# Rigid-QFN-2.net
KiCad netlist of a schematic drawn in Altium Designer
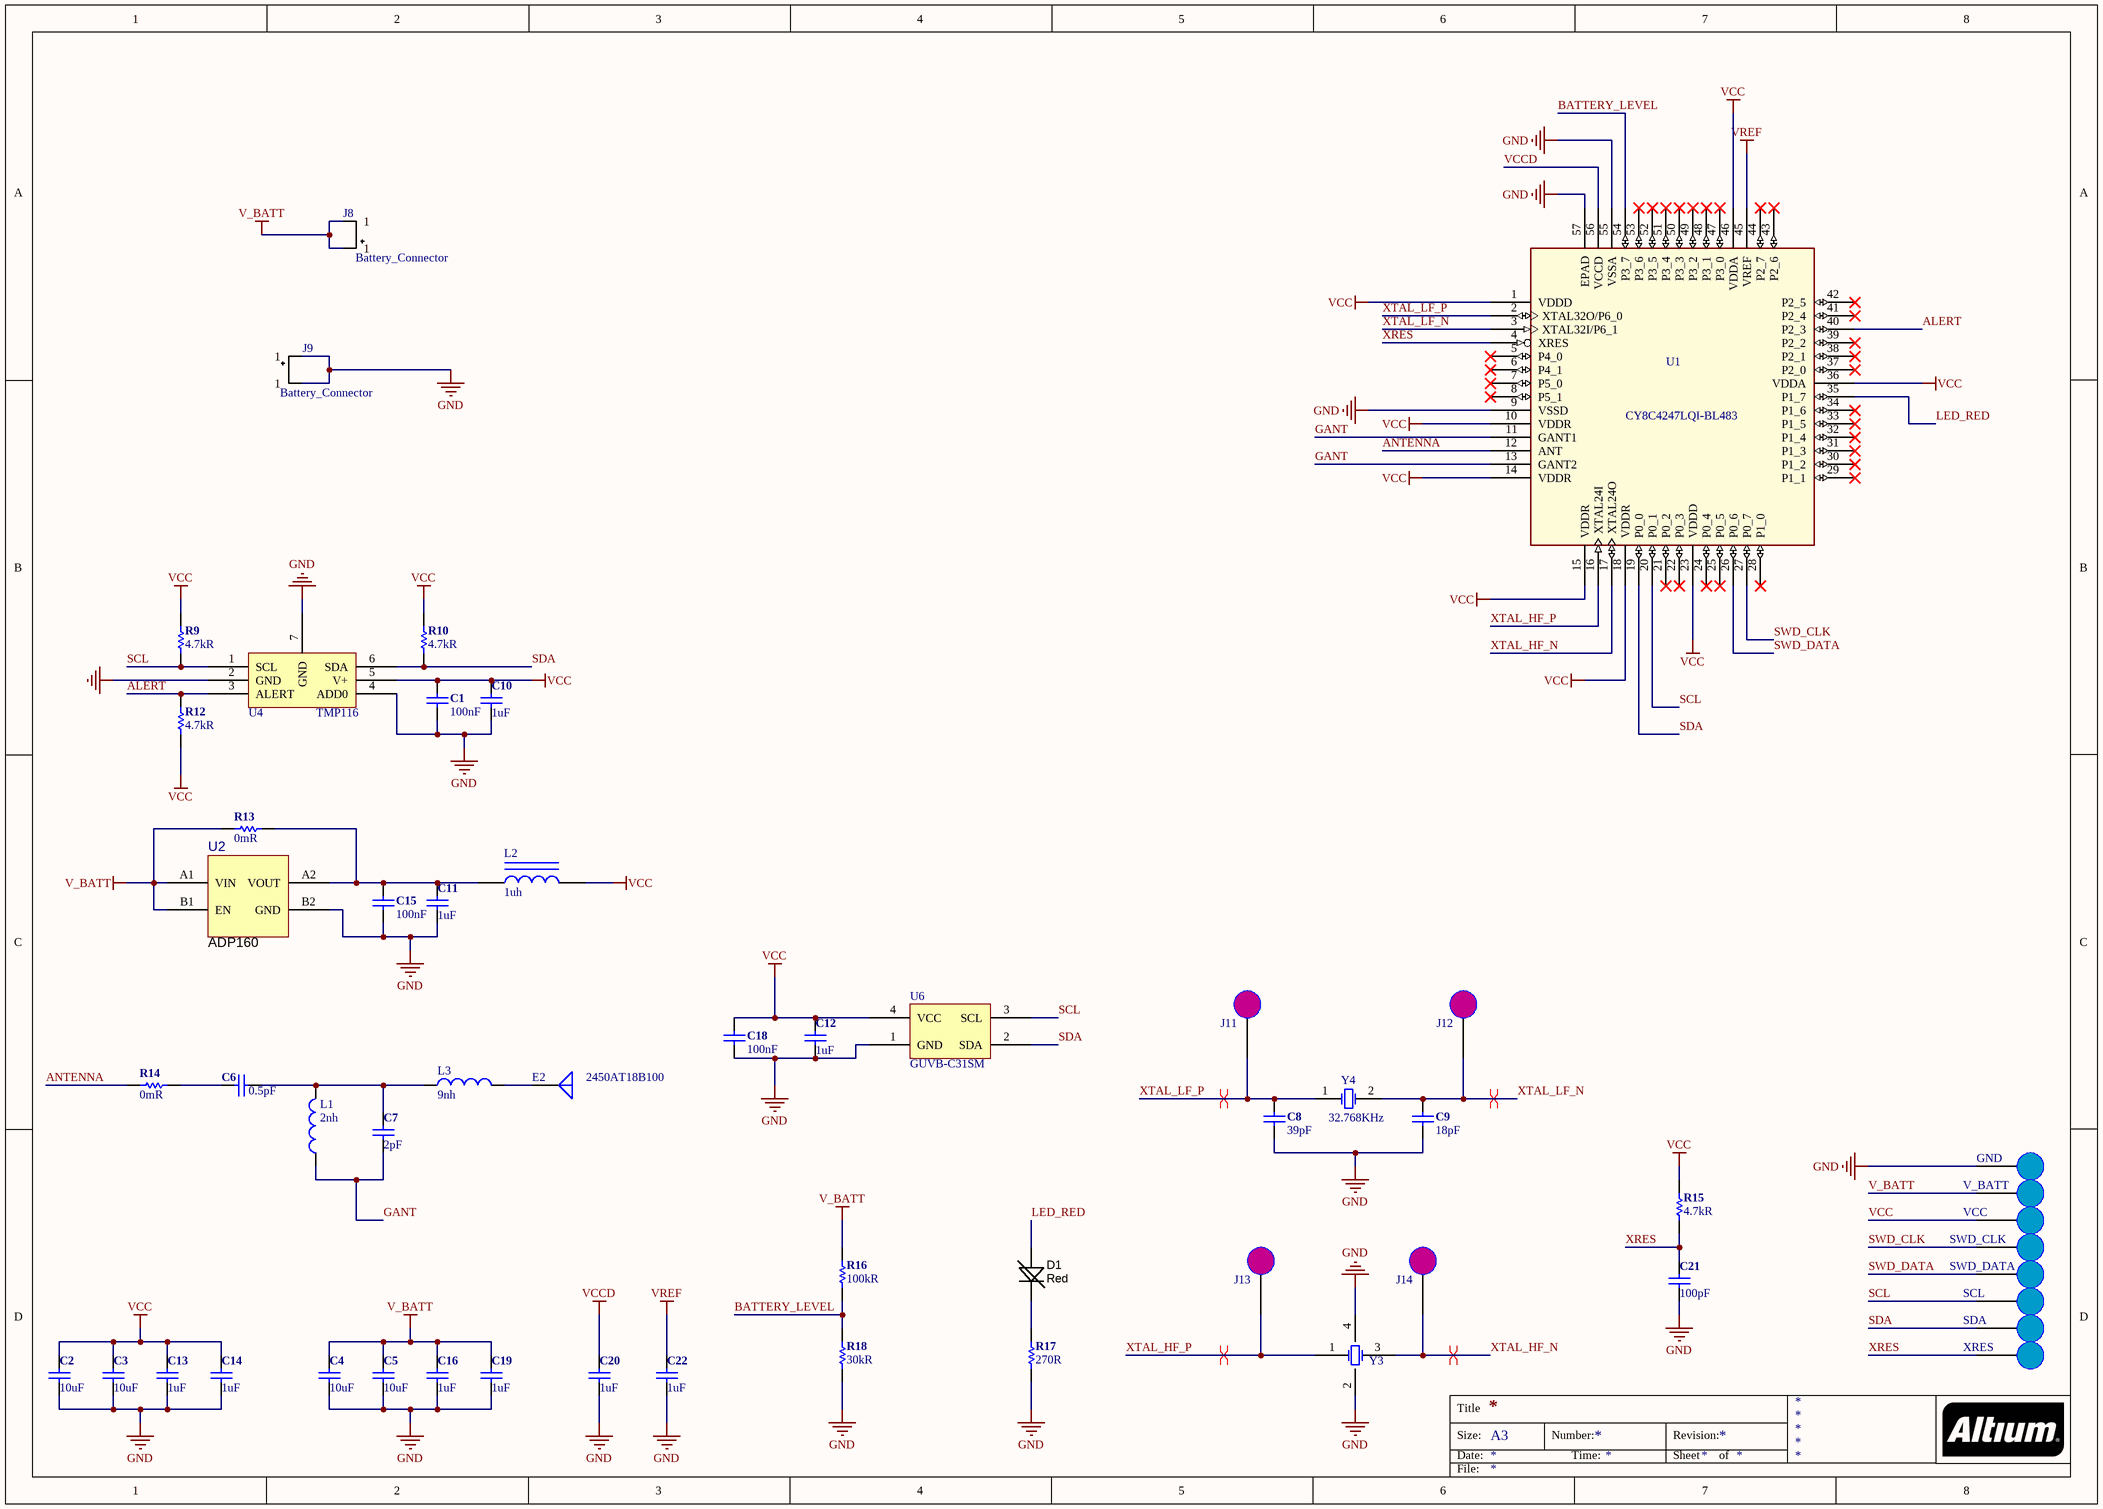
[diagram p0: Rigid-QFN-2.SchDoc]

(export (version "E")
  (design (tool "Eeschema 10.0.6"))
  (components
    (comp (ref "C1")
      (value "100nF")
      (footprint "CAP_0402(1005)_M")
      (description "___ OHM ___ mW 0402(1005) SMD")
      (fields
        (field (name "MANUFACTURER") "Yageo")
        (field (name "MANUFACTURER PART NUMBER") "CC0402ZRY5V6BB104")
      )
      (libsource (lib "tempsensor") (part "C-0402(1005)"))
    )
    (comp (ref "C2")
      (value "10uF")
      (footprint "CAP_0402(1005)_M")
      (description "___ OHM ___ mW 0402(1005) SMD")
      (fields
        (field (name "MANUFACTURER") "Murata")
        (field (name "MANUFACTURER PART NUMBER") "GRM155R60J106ME15D")
      )
      (libsource (lib "tempsensor") (part "C-0402(1005)"))
    )
    (comp (ref "C3")
      (value "10uF")
      (footprint "CAP_0402(1005)_M")
      (description "___ OHM ___ mW 0402(1005) SMD")
      (fields
        (field (name "MANUFACTURER") "Murata")
        (field (name "MANUFACTURER PART NUMBER") "GRM155R60J106ME15D")
      )
      (libsource (lib "tempsensor") (part "C-0402(1005)"))
    )
    (comp (ref "C4")
      (value "10uF")
      (footprint "CAP_0402(1005)_M")
      (description "___ OHM ___ mW 0402(1005) SMD")
      (fields
        (field (name "MANUFACTURER") "Murata")
        (field (name "MANUFACTURER PART NUMBER") "GRM155R60J106ME15D")
      )
      (libsource (lib "tempsensor") (part "C-0402(1005)"))
    )
    (comp (ref "C5")
      (value "10uF")
      (footprint "CAP_0402(1005)_M")
      (description "___ OHM ___ mW 0402(1005) SMD")
      (fields
        (field (name "MANUFACTURER") "Murata")
        (field (name "MANUFACTURER PART NUMBER") "GRM155R60J106ME15D")
      )
      (libsource (lib "tempsensor") (part "C-0402(1005)"))
    )
    (comp (ref "C6")
      (value "0.5pF")
      (footprint "CAP_0402(1005)_M")
      (description "___ OHM ___ mW 0402(1005) SMD")
      (fields
        (field (name "MANUFACTURER") "Murata")
        (field (name "MANUFACTURER PART NUMBER") "GJM1555C1HR50WB01D")
      )
      (libsource (lib "tempsensor") (part "C-0402(1005)"))
    )
    (comp (ref "C7")
      (value "2pF")
      (footprint "CAP_0402(1005)_M")
      (description "___ OHM ___ mW 0402(1005) SMD")
      (fields
        (field (name "MANUFACTURER") "Murata")
        (field (name "MANUFACTURER PART NUMBER") "GJM1555C1H2R0BB01D")
      )
      (libsource (lib "tempsensor") (part "C-0402(1005)"))
    )
    (comp (ref "C8")
      (value "39pF")
      (footprint "CAP_0402(1005)_M")
      (description "___ OHM ___ mW 0402(1005) SMD")
      (fields
        (field (name "MANUFACTURER") "KEMET")
        (field (name "MANUFACTURER PART NUMBER") "CBR04C390F5GAC")
      )
      (libsource (lib "tempsensor") (part "C-0402(1005)"))
    )
    (comp (ref "C9")
      (value "18pF")
      (footprint "CAP_0402(1005)_M")
      (description "___ OHM ___ mW 0402(1005) SMD")
      (fields
        (field (name "MANUFACTURER") "Murata")
        (field (name "MANUFACTURER PART NUMBER") "GJM1555C1H180FB01D")
      )
      (libsource (lib "tempsensor") (part "C-0402(1005)"))
    )
    (comp (ref "C10")
      (value "1uF")
      (footprint "CAP_0402(1005)_M")
      (description "___ OHM ___ mW 0402(1005) SMD")
      (fields
        (field (name "MANUFACTURER") "KEMET")
        (field (name "MANUFACTURER PART NUMBER") "C0402C105K8PACTU")
      )
      (libsource (lib "tempsensor") (part "C-0402(1005)"))
    )
    (comp (ref "C11")
      (value "1uF")
      (footprint "CAP_0402(1005)_M")
      (description "___ OHM ___ mW 0402(1005) SMD")
      (fields
        (field (name "MANUFACTURER") "KEMET")
        (field (name "MANUFACTURER PART NUMBER") "C0402C105K8PACTU")
      )
      (libsource (lib "tempsensor") (part "C-0402(1005)"))
    )
    (comp (ref "C12")
      (value "1uF")
      (footprint "CAP_0402(1005)_M")
      (description "___ OHM ___ mW 0402(1005) SMD")
      (fields
        (field (name "MANUFACTURER") "KEMET")
        (field (name "MANUFACTURER PART NUMBER") "C0402C105K8PACTU")
      )
      (libsource (lib "tempsensor") (part "C-0402(1005)"))
    )
    (comp (ref "C13")
      (value "1uF")
      (footprint "CAP_0402(1005)_M")
      (description "___ OHM ___ mW 0402(1005) SMD")
      (fields
        (field (name "MANUFACTURER") "KEMET")
        (field (name "MANUFACTURER PART NUMBER") "C0402C105K8PACTU")
      )
      (libsource (lib "tempsensor") (part "C-0402(1005)"))
    )
    (comp (ref "C14")
      (value "1uF")
      (footprint "CAP_0402(1005)_M")
      (description "___ OHM ___ mW 0402(1005) SMD")
      (fields
        (field (name "MANUFACTURER") "KEMET")
        (field (name "MANUFACTURER PART NUMBER") "C0402C105K8PACTU")
      )
      (libsource (lib "tempsensor") (part "C-0402(1005)"))
    )
    (comp (ref "C15")
      (value "100nF")
      (footprint "CAP_0402(1005)_M")
      (description "___ OHM ___ mW 0402(1005) SMD")
      (fields
        (field (name "MANUFACTURER") "Yageo")
        (field (name "MANUFACTURER PART NUMBER") "CC0402ZRY5V6BB104")
      )
      (libsource (lib "tempsensor") (part "C-0402(1005)"))
    )
    (comp (ref "C16")
      (value "1uF")
      (footprint "CAP_0402(1005)_M")
      (description "___ OHM ___ mW 0402(1005) SMD")
      (fields
        (field (name "MANUFACTURER") "KEMET")
        (field (name "MANUFACTURER PART NUMBER") "C0402C105K8PACTU")
      )
      (libsource (lib "tempsensor") (part "C-0402(1005)"))
    )
    (comp (ref "C18")
      (value "100nF")
      (footprint "CAP_0402(1005)_M")
      (description "___ OHM ___ mW 0402(1005) SMD")
      (fields
        (field (name "MANUFACTURER") "Yageo")
        (field (name "MANUFACTURER PART NUMBER") "CC0402ZRY5V6BB104")
      )
      (libsource (lib "tempsensor") (part "C-0402(1005)"))
    )
    (comp (ref "C19")
      (value "1uF")
      (footprint "CAP_0402(1005)_M")
      (description "___ OHM ___ mW 0402(1005) SMD")
      (fields
        (field (name "MANUFACTURER") "KEMET")
        (field (name "MANUFACTURER PART NUMBER") "C0402C105K8PACTU")
      )
      (libsource (lib "tempsensor") (part "C-0402(1005)"))
    )
    (comp (ref "C20")
      (value "1uF")
      (footprint "CAP_0402(1005)_M")
      (description "___ OHM ___ mW 0402(1005) SMD")
      (fields
        (field (name "MANUFACTURER") "KEMET")
        (field (name "MANUFACTURER PART NUMBER") "C0402C105K8PACTU")
      )
      (libsource (lib "tempsensor") (part "C-0402(1005)"))
    )
    (comp (ref "C21")
      (value "100pF")
      (footprint "CAP_0402(1005)_M")
      (description "___ OHM ___ mW 0402(1005) SMD")
      (fields
        (field (name "MANUFACTURER") "Wurth Electronics")
        (field (name "MANUFACTURER PART NUMBER") "885012005013")
      )
      (libsource (lib "tempsensor") (part "C-0402(1005)"))
    )
    (comp (ref "C22")
      (value "1uF")
      (footprint "CAP_0402(1005)_M")
      (description "___ OHM ___ mW 0402(1005) SMD")
      (fields
        (field (name "MANUFACTURER") "KEMET")
        (field (name "MANUFACTURER PART NUMBER") "C0402C105K8PACTU")
      )
      (libsource (lib "tempsensor") (part "C-0402(1005)"))
    )
    (comp (ref "D1")
      (value "Red")
      (footprint "LED_0402(1005)")
      (description "LED, 0402(1005) SMD")
      (fields
        (field (name "MANUFACTURER") "Kingbright")
        (field (name "MANUFACTURER PART NUMBER") "APHHS1005SURCK")
      )
      (libsource (lib "tempsensor") (part "LED_0402(1005)"))
    )
    (comp (ref "E2")
      (value "2450AT18B100")
      (footprint "2450AT18B100")
      (description "2.4 GHz BLE Antenna")
      (fields
        (field (name "MANUFACTURER") "Johanson")
        (field (name "MANUFACTURER PART NUMBER") "2450AT18B100E")
      )
      (libsource (lib "tempsensor") (part "2450AT18B100"))
    )
    (comp (ref "GND")
      (value "Probe-Pin Pad")
      (footprint "Pogo-Pin-Pad")
      (libsource (lib "tempsensor") (part "Probe-Pin Pad"))
    )
    (comp (ref "J8")
      (value "Battery_Connector")
      (footprint "Battery_PAD")
      (libsource (lib "tempsensor") (part "Battery_Connector"))
    )
    (comp (ref "J9")
      (value "Battery_Connector")
      (footprint "Battery_PAD")
      (libsource (lib "tempsensor") (part "Battery_Connector"))
    )
    (comp (ref "J11")
      (value "Probe-CLOCK")
      (footprint "Pogo-CLOCK-PAD")
      (libsource (lib "tempsensor") (part "Probe-CLOCK"))
    )
    (comp (ref "J12")
      (value "Probe-CLOCK")
      (footprint "Pogo-CLOCK-PAD")
      (libsource (lib "tempsensor") (part "Probe-CLOCK"))
    )
    (comp (ref "J13")
      (value "Probe-CLOCK")
      (footprint "Pogo-CLOCK-PAD")
      (libsource (lib "tempsensor") (part "Probe-CLOCK"))
    )
    (comp (ref "J14")
      (value "Probe-CLOCK")
      (footprint "Pogo-CLOCK-PAD")
      (libsource (lib "tempsensor") (part "Probe-CLOCK"))
    )
    (comp (ref "L1")
      (value "2nh")
      (footprint "IND_0402(1005)_M")
      (fields
        (field (name "MANUFACTURER") "Abracon")
        (field (name "MANUFACTURER PART NUMBER") "AISC-0402-2N0J-T")
        (field (name "TOLERANCE") "5%")
      )
      (libsource (lib "tempsensor") (part "I-0402(1005)"))
    )
    (comp (ref "L2")
      (value "1uh")
      (footprint "IND_0402(1005)_M")
      (description "Magnetic-Core Inductor")
      (fields
        (field (name "MANUFACTURER") "TDK")
        (field (name "MANUFACTURER PART NUMBER") "MLZ1005M1R0WT000")
      )
      (libsource (lib "tempsensor") (part "Inductor Iron"))
    )
    (comp (ref "L3")
      (value "9nh")
      (footprint "IND_0402(1005)_M")
      (fields
        (field (name "MANUFACTURER") "Murata")
        (field (name "MANUFACTURER PART NUMBER") "LQW15AN9N0G80D")
        (field (name "TOLERANCE") "2%")
      )
      (libsource (lib "tempsensor") (part "I-0402(1005)"))
    )
    (comp (ref "R9")
      (value "4.7kR")
      (footprint "RES_0402(1005)_M")
      (description "___ OHM ___ mW 0402(1005) SMD")
      (fields
        (field (name "MANUFACTURER") "Yageo")
        (field (name "MANUFACTURER PART NUMBER") "RC0402JR-074K7P")
      )
      (libsource (lib "tempsensor") (part "R-0402(1005)"))
    )
    (comp (ref "R10")
      (value "4.7kR")
      (footprint "RES_0402(1005)_M")
      (description "___ OHM ___ mW 0402(1005) SMD")
      (fields
        (field (name "MANUFACTURER") "Yageo")
        (field (name "MANUFACTURER PART NUMBER") "RC0402JR-074K7P")
      )
      (libsource (lib "tempsensor") (part "R-0402(1005)"))
    )
    (comp (ref "R12")
      (value "4.7kR")
      (footprint "RES_0402(1005)_M")
      (description "___ OHM ___ mW 0402(1005) SMD")
      (fields
        (field (name "MANUFACTURER") "Yageo")
        (field (name "MANUFACTURER PART NUMBER") "RC0402JR-074K7P")
      )
      (libsource (lib "tempsensor") (part "R-0402(1005)"))
    )
    (comp (ref "R13")
      (value "0mR")
      (footprint "RES_0402(1005)_M")
      (description "___ OHM ___ mW 0402(1005) SMD")
      (fields
        (field (name "MANUFACTURER") "Yageo")
        (field (name "MANUFACTURER PART NUMBER") "AC0402JR-070RL")
      )
      (libsource (lib "tempsensor") (part "R-0402(1005)"))
    )
    (comp (ref "R14")
      (value "0mR")
      (footprint "RES_0402(1005)_M")
      (description "___ OHM ___ mW 0402(1005) SMD")
      (fields
        (field (name "MANUFACTURER") "Yageo")
        (field (name "MANUFACTURER PART NUMBER") "AC0402JR-070RL")
      )
      (libsource (lib "tempsensor") (part "R-0402(1005)"))
    )
    (comp (ref "R15")
      (value "4.7kR")
      (footprint "RES_0402(1005)_M")
      (description "___ OHM ___ mW 0402(1005) SMD")
      (fields
        (field (name "MANUFACTURER") "Yageo")
        (field (name "MANUFACTURER PART NUMBER") "RC0402JR-074K7P")
      )
      (libsource (lib "tempsensor") (part "R-0402(1005)"))
    )
    (comp (ref "R16")
      (value "100kR")
      (footprint "RES_0402(1005)_M")
      (description "___ OHM ___ mW 0402(1005) SMD")
      (fields
        (field (name "MANUFACTURER") "Yageo")
        (field (name "MANUFACTURER PART NUMBER") "AC0402JR-07100KL")
      )
      (libsource (lib "tempsensor") (part "R-0402(1005)"))
    )
    (comp (ref "R17")
      (value "270R")
      (footprint "RES_0402(1005)_M")
      (description "___ OHM ___ mW 0402(1005) SMD")
      (fields
        (field (name "MANUFACTURER") "Yageo")
        (field (name "MANUFACTURER PART NUMBER") "RC0402JR-07270RL")
      )
      (libsource (lib "tempsensor") (part "R-0402(1005)"))
    )
    (comp (ref "R18")
      (value "30kR")
      (footprint "RES_0402(1005)_M")
      (description "___ OHM ___ mW 0402(1005) SMD")
      (fields
        (field (name "MANUFACTURER") "Yageo")
        (field (name "MANUFACTURER PART NUMBER") "RC0402JR-0730KL")
      )
      (libsource (lib "tempsensor") (part "R-0402(1005)"))
    )
    (comp (ref "SCL")
      (value "Probe-Pin Pad")
      (footprint "Pogo-Pin-Pad")
      (libsource (lib "tempsensor") (part "Probe-Pin Pad"))
    )
    (comp (ref "SDA")
      (value "Probe-Pin Pad")
      (footprint "Pogo-Pin-Pad")
      (libsource (lib "tempsensor") (part "Probe-Pin Pad"))
    )
    (comp (ref "SWD_CLK")
      (value "Probe-Pin Pad")
      (footprint "Pogo-Pin-Pad")
      (libsource (lib "tempsensor") (part "Probe-Pin Pad"))
    )
    (comp (ref "SWD_DATA")
      (value "Probe-Pin Pad")
      (footprint "Pogo-Pin-Pad")
      (libsource (lib "tempsensor") (part "Probe-Pin Pad"))
    )
    (comp (ref "U1")
      (value "CY8C4247LQI-BL483")
      (footprint "QFN40P700X700X60-57N")
      (fields (field (name "MANUFACTURER") "Cypress"))
      (libsource (lib "tempsensor") (part "CY8C4247LQI-BL483"))
    )
    (comp (ref "U2")
      (value "ADP160")
      (footprint "ADP160")
      (description "3V LDO")
      (fields
        (field (name "MANUFACTURER") "Analog Devices")
        (field (name "MANUFACTURER PART NUMBER") "ADP160ACBZ-3.0-R7")
      )
      (libsource (lib "tempsensor") (part "ADP160"))
    )
    (comp (ref "U4")
      (value "TMP116")
      (footprint "WSON-6")
      (description "TI Digital I2C Temperature Sensor")
      (fields
        (field (name "MANUFACTURER") "Texas Instruments")
        (field (name "MANUFACTURER PART NUMBER") "TMP116AIDRVT")
      )
      (libsource (lib "tempsensor") (part "TMP116"))
    )
    (comp (ref "U6")
      (value "GUVB-C31SM")
      (footprint "GUVB-C31SM")
      (libsource (lib "tempsensor") (part "GUVB-C31SM"))
    )
    (comp (ref "VCC")
      (value "Probe-Pin Pad")
      (footprint "Pogo-Pin-Pad")
      (libsource (lib "tempsensor") (part "Probe-Pin Pad"))
    )
    (comp (ref "V_BATT")
      (value "Probe-Pin Pad")
      (footprint "Pogo-Pin-Pad")
      (libsource (lib "tempsensor") (part "Probe-Pin Pad"))
    )
    (comp (ref "XRES")
      (value "Probe-Pin Pad")
      (footprint "Pogo-Pin-Pad")
      (libsource (lib "tempsensor") (part "Probe-Pin Pad"))
    )
    (comp (ref "Y3")
      (value "ECX-2236")
      (footprint "ECX-2236")
      (description "24 MHz Crystal")
      (fields
        (field (name "MANUFACTURER") "ECS International")
        (field (name "MANUFACTURER PART NUMBER") "ECS-240-8-36CKM-TR")
      )
      (libsource (lib "tempsensor") (part "ECX-2236"))
    )
    (comp (ref "Y4")
      (value "32.768KHz")
      (footprint "ABS05")
      (description "Crystal Oscillator")
      (fields
        (field (name "MANUFACTURER") "Abracon")
        (field (name "MANUFACTURER PART NUMBER") "ABS05-32.768KHZ-T")
      )
      (libsource (lib "tempsensor") (part "ABS05"))
    )
  )
  (nets
    (net (code "1") (name "/ALERT") (class "Default")
      (node (ref "R12") (pin "2") (pinfunction "2_2") (pintype "passive"))
      (node (ref "U1") (pin "40") (pinfunction "P2_3_40") (pintype "bidirectional"))
      (node (ref "U4") (pin "3") (pinfunction "ALERT_3") (pintype "passive"))
    )
    (net (code "2") (name "/ANTENNA") (class "Default")
      (node (ref "R14") (pin "1") (pinfunction "1_1") (pintype "passive"))
      (node (ref "U1") (pin "12") (pinfunction "ANT_12") (pintype "passive"))
    )
    (net (code "3") (name "/BATTERY_LEVEL") (class "Default")
      (node (ref "R16") (pin "2") (pinfunction "2_2") (pintype "passive"))
      (node (ref "R18") (pin "1") (pinfunction "1_1") (pintype "passive"))
      (node (ref "U1") (pin "54") (pinfunction "P3_7_54") (pintype "bidirectional"))
    )
    (net (code "4") (name "/GANT") (class "Default")
      (node (ref "C7") (pin "2") (pinfunction "2_2") (pintype "passive"))
      (node (ref "L1") (pin "1") (pinfunction "1_1") (pintype "passive"))
      (node (ref "U1") (pin "11") (pinfunction "GANT1_11") (pintype "power_in"))
      (node (ref "U1") (pin "13") (pinfunction "GANT2_13") (pintype "power_in"))
    )
    (net (code "5") (name "/LED_RED") (class "Default")
      (node (ref "D1") (pin "A") (pinfunction "A_A") (pintype "passive"))
      (node (ref "U1") (pin "35") (pinfunction "P1_7_35") (pintype "bidirectional"))
    )
    (net (code "6") (name "/SCL") (class "Default")
      (node (ref "R9") (pin "1") (pinfunction "1_1") (pintype "passive"))
      (node (ref "SCL") (pin "1") (pinfunction "1_1") (pintype "passive"))
      (node (ref "U1") (pin "20") (pinfunction "P0_1_20") (pintype "bidirectional"))
      (node (ref "U4") (pin "1") (pinfunction "SCL_1") (pintype "passive"))
      (node (ref "U6") (pin "3") (pinfunction "SCL_3") (pintype "passive"))
    )
    (net (code "7") (name "/SDA") (class "Default")
      (node (ref "R10") (pin "1") (pinfunction "1_1") (pintype "passive"))
      (node (ref "SDA") (pin "1") (pinfunction "1_1") (pintype "passive"))
      (node (ref "U1") (pin "19") (pinfunction "P0_0_19") (pintype "bidirectional"))
      (node (ref "U4") (pin "6") (pinfunction "SDA_6") (pintype "passive"))
      (node (ref "U6") (pin "2") (pinfunction "SDA_2") (pintype "passive"))
    )
    (net (code "8") (name "/SWD_CLK") (class "Default")
      (node (ref "SWD_CLK") (pin "1") (pinfunction "1_1") (pintype "passive"))
      (node (ref "U1") (pin "27") (pinfunction "P0_7_27") (pintype "bidirectional"))
    )
    (net (code "9") (name "/SWD_DATA") (class "Default")
      (node (ref "SWD_DATA") (pin "1") (pinfunction "1_1") (pintype "passive"))
      (node (ref "U1") (pin "26") (pinfunction "P0_6_26") (pintype "bidirectional"))
    )
    (net (code "10") (name "/XRES") (class "Default")
      (node (ref "C21") (pin "1") (pinfunction "1_1") (pintype "passive"))
      (node (ref "R15") (pin "2") (pinfunction "2_2") (pintype "passive"))
      (node (ref "U1") (pin "4") (pinfunction "XRES_4") (pintype "input"))
      (node (ref "XRES") (pin "1") (pinfunction "1_1") (pintype "passive"))
    )
    (net (code "11") (name "/XTAL_HF_N") (class "Default")
      (node (ref "J14") (pin "1") (pinfunction "1_1") (pintype "passive"))
      (node (ref "U1") (pin "17") (pinfunction "XTAL24O_17") (pintype "bidirectional"))
      (node (ref "Y3") (pin "3") (pinfunction "OSC2_3") (pintype "passive"))
    )
    (net (code "12") (name "/XTAL_HF_P") (class "Default")
      (node (ref "J13") (pin "1") (pinfunction "1_1") (pintype "passive"))
      (node (ref "U1") (pin "16") (pinfunction "XTAL24I_16") (pintype "input"))
      (node (ref "Y3") (pin "1") (pinfunction "OSC1_1") (pintype "passive"))
    )
    (net (code "13") (name "/XTAL_LF_N") (class "Default")
      (node (ref "C9") (pin "1") (pinfunction "1_1") (pintype "passive"))
      (node (ref "J12") (pin "1") (pinfunction "1_1") (pintype "passive"))
      (node (ref "U1") (pin "3") (pinfunction "XTAL32I/P6_1_3") (pintype "input"))
      (node (ref "Y4") (pin "2") (pinfunction "OSC2_2") (pintype "passive"))
    )
    (net (code "14") (name "/XTAL_LF_P") (class "Default")
      (node (ref "C8") (pin "1") (pinfunction "1_1") (pintype "passive"))
      (node (ref "J11") (pin "1") (pinfunction "1_1") (pintype "passive"))
      (node (ref "U1") (pin "2") (pinfunction "XTAL32O/P6_0_2") (pintype "bidirectional"))
      (node (ref "Y4") (pin "1") (pinfunction "OSC1_1") (pintype "passive"))
    )
    (net (code "15") (name "GND") (class "Default")
      (node (ref "C1") (pin "2") (pinfunction "2_2") (pintype "passive"))
      (node (ref "C10") (pin "2") (pinfunction "2_2") (pintype "passive"))
      (node (ref "C11") (pin "2") (pinfunction "2_2") (pintype "passive"))
      (node (ref "C12") (pin "2") (pinfunction "2_2") (pintype "passive"))
      (node (ref "C13") (pin "2") (pinfunction "2_2") (pintype "passive"))
      (node (ref "C14") (pin "2") (pinfunction "2_2") (pintype "passive"))
      (node (ref "C15") (pin "2") (pinfunction "2_2") (pintype "passive"))
      (node (ref "C16") (pin "2") (pinfunction "2_2") (pintype "passive"))
      (node (ref "C18") (pin "2") (pinfunction "2_2") (pintype "passive"))
      (node (ref "C19") (pin "2") (pinfunction "2_2") (pintype "passive"))
      (node (ref "C2") (pin "2") (pinfunction "2_2") (pintype "passive"))
      (node (ref "C20") (pin "2") (pinfunction "2_2") (pintype "passive"))
      (node (ref "C21") (pin "2") (pinfunction "2_2") (pintype "passive"))
      (node (ref "C22") (pin "2") (pinfunction "2_2") (pintype "passive"))
      (node (ref "C3") (pin "2") (pinfunction "2_2") (pintype "passive"))
      (node (ref "C4") (pin "2") (pinfunction "2_2") (pintype "passive"))
      (node (ref "C5") (pin "2") (pinfunction "2_2") (pintype "passive"))
      (node (ref "C8") (pin "2") (pinfunction "2_2") (pintype "passive"))
      (node (ref "C9") (pin "2") (pinfunction "2_2") (pintype "passive"))
      (node (ref "GND") (pin "1") (pinfunction "1_1") (pintype "passive"))
      (node (ref "J9") (pin "1") (pinfunction "1_1") (pintype "passive"))
      (node (ref "R17") (pin "2") (pinfunction "2_2") (pintype "passive"))
      (node (ref "R18") (pin "2") (pinfunction "2_2") (pintype "passive"))
      (node (ref "U1") (pin "55") (pinfunction "VSSA_55") (pintype "power_in"))
      (node (ref "U1") (pin "57") (pinfunction "EPAD_57") (pintype "power_in"))
      (node (ref "U1") (pin "9") (pinfunction "VSSD_9") (pintype "power_in"))
      (node (ref "U2") (pin "B2") (pinfunction "GND_B2") (pintype "passive"))
      (node (ref "U4") (pin "2") (pinfunction "GND_2") (pintype "passive"))
      (node (ref "U4") (pin "4") (pinfunction "ADD0_4") (pintype "passive"))
      (node (ref "U4") (pin "7") (pinfunction "GND_7") (pintype "passive"))
      (node (ref "U6") (pin "1") (pinfunction "GND_1") (pintype "passive"))
      (node (ref "Y3") (pin "2") (pinfunction "GND_2") (pintype "passive"))
      (node (ref "Y3") (pin "4") (pinfunction "GND_4") (pintype "passive"))
    )
    (net (code "16") (name "Net-(C6-Pad1)") (class "Default")
      (node (ref "C6") (pin "1") (pinfunction "1_1") (pintype "passive"))
      (node (ref "R14") (pin "2") (pinfunction "2_2") (pintype "passive"))
    )
    (net (code "17") (name "Net-(C6-Pad2)") (class "Default")
      (node (ref "C6") (pin "2") (pinfunction "2_2") (pintype "passive"))
      (node (ref "C7") (pin "1") (pinfunction "1_1") (pintype "passive"))
      (node (ref "L1") (pin "2") (pinfunction "2_2") (pintype "passive"))
      (node (ref "L3") (pin "1") (pinfunction "1_1") (pintype "passive"))
    )
    (net (code "18") (name "Net-(D1-PadK)") (class "Default")
      (node (ref "D1") (pin "K") (pinfunction "K_K") (pintype "passive"))
      (node (ref "R17") (pin "1") (pinfunction "1_1") (pintype "passive"))
    )
    (net (code "19") (name "Net-(E2-A)") (class "Default")
      (node (ref "E2") (pin "1") (pinfunction "A_1") (pintype "passive"))
      (node (ref "L3") (pin "2") (pinfunction "2_2") (pintype "passive"))
    )
    (net (code "20") (name "Net-(U2-VOUT)") (class "Default")
      (node (ref "C11") (pin "1") (pinfunction "1_1") (pintype "passive"))
      (node (ref "C15") (pin "1") (pinfunction "1_1") (pintype "passive"))
      (node (ref "L2") (pin "1") (pinfunction "1_1") (pintype "passive"))
      (node (ref "R13") (pin "2") (pinfunction "2_2") (pintype "passive"))
      (node (ref "U2") (pin "A2") (pinfunction "VOUT_A2") (pintype "passive"))
    )
    (net (code "21") (name "VCC") (class "Default")
      (node (ref "C1") (pin "1") (pinfunction "1_1") (pintype "passive"))
      (node (ref "C10") (pin "1") (pinfunction "1_1") (pintype "passive"))
      (node (ref "C12") (pin "1") (pinfunction "1_1") (pintype "passive"))
      (node (ref "C13") (pin "1") (pinfunction "1_1") (pintype "passive"))
      (node (ref "C14") (pin "1") (pinfunction "1_1") (pintype "passive"))
      (node (ref "C18") (pin "1") (pinfunction "1_1") (pintype "passive"))
      (node (ref "C2") (pin "1") (pinfunction "1_1") (pintype "passive"))
      (node (ref "C3") (pin "1") (pinfunction "1_1") (pintype "passive"))
      (node (ref "L2") (pin "2") (pinfunction "2_2") (pintype "passive"))
      (node (ref "R10") (pin "2") (pinfunction "2_2") (pintype "passive"))
      (node (ref "R12") (pin "1") (pinfunction "1_1") (pintype "passive"))
      (node (ref "R15") (pin "1") (pinfunction "1_1") (pintype "passive"))
      (node (ref "R9") (pin "2") (pinfunction "2_2") (pintype "passive"))
      (node (ref "U1") (pin "1") (pinfunction "VDDD_1") (pintype "power_in"))
      (node (ref "U1") (pin "10") (pinfunction "VDDR_10") (pintype "power_in"))
      (node (ref "U1") (pin "14") (pinfunction "VDDR_14") (pintype "power_in"))
      (node (ref "U1") (pin "15") (pinfunction "VDDR_15") (pintype "power_in"))
      (node (ref "U1") (pin "18") (pinfunction "VDDR_18") (pintype "power_in"))
      (node (ref "U1") (pin "23") (pinfunction "VDDD_23") (pintype "power_in"))
      (node (ref "U1") (pin "36") (pinfunction "VDDA_36") (pintype "power_in"))
      (node (ref "U1") (pin "46") (pinfunction "VDDA_46") (pintype "power_in"))
      (node (ref "U4") (pin "5") (pinfunction "V+_5") (pintype "passive"))
      (node (ref "U6") (pin "4") (pinfunction "VCC_4") (pintype "passive"))
      (node (ref "VCC") (pin "1") (pinfunction "1_1") (pintype "passive"))
    )
    (net (code "22") (name "VCCD") (class "Default")
      (node (ref "C20") (pin "1") (pinfunction "1_1") (pintype "passive"))
      (node (ref "U1") (pin "56") (pinfunction "VCCD_56") (pintype "power_in"))
    )
    (net (code "23") (name "VREF") (class "Default")
      (node (ref "C22") (pin "1") (pinfunction "1_1") (pintype "passive"))
      (node (ref "U1") (pin "45") (pinfunction "VREF_45") (pintype "power_in"))
    )
    (net (code "24") (name "V_BATT") (class "Default")
      (node (ref "C16") (pin "1") (pinfunction "1_1") (pintype "passive"))
      (node (ref "C19") (pin "1") (pinfunction "1_1") (pintype "passive"))
      (node (ref "C4") (pin "1") (pinfunction "1_1") (pintype "passive"))
      (node (ref "C5") (pin "1") (pinfunction "1_1") (pintype "passive"))
      (node (ref "J8") (pin "1") (pinfunction "1_1") (pintype "passive"))
      (node (ref "R13") (pin "1") (pinfunction "1_1") (pintype "passive"))
      (node (ref "R16") (pin "1") (pinfunction "1_1") (pintype "passive"))
      (node (ref "U2") (pin "A1") (pinfunction "VIN_A1") (pintype "passive"))
      (node (ref "U2") (pin "B1") (pinfunction "EN_B1") (pintype "passive"))
      (node (ref "V_BATT") (pin "1") (pinfunction "1_1") (pintype "passive"))
    )
    (net (code "25") (name "unconnected-(U1-P0_2-Pad21)") (class "Default")
      (node (ref "U1") (pin "21") (pinfunction "P0_2_21") (pintype "bidirectional+no_connect"))
    )
    (net (code "26") (name "unconnected-(U1-P0_3-Pad22)") (class "Default")
      (node (ref "U1") (pin "22") (pinfunction "P0_3_22") (pintype "bidirectional+no_connect"))
    )
    (net (code "27") (name "unconnected-(U1-P0_4-Pad24)") (class "Default")
      (node (ref "U1") (pin "24") (pinfunction "P0_4_24") (pintype "bidirectional+no_connect"))
    )
    (net (code "28") (name "unconnected-(U1-P0_5-Pad25)") (class "Default")
      (node (ref "U1") (pin "25") (pinfunction "P0_5_25") (pintype "bidirectional+no_connect"))
    )
    (net (code "29") (name "unconnected-(U1-P1_0-Pad28)") (class "Default")
      (node (ref "U1") (pin "28") (pinfunction "P1_0_28") (pintype "bidirectional+no_connect"))
    )
    (net (code "30") (name "unconnected-(U1-P1_1-Pad29)") (class "Default")
      (node (ref "U1") (pin "29") (pinfunction "P1_1_29") (pintype "bidirectional+no_connect"))
    )
    (net (code "31") (name "unconnected-(U1-P1_2-Pad30)") (class "Default")
      (node (ref "U1") (pin "30") (pinfunction "P1_2_30") (pintype "bidirectional+no_connect"))
    )
    (net (code "32") (name "unconnected-(U1-P1_3-Pad31)") (class "Default")
      (node (ref "U1") (pin "31") (pinfunction "P1_3_31") (pintype "bidirectional+no_connect"))
    )
    (net (code "33") (name "unconnected-(U1-P1_4-Pad32)") (class "Default")
      (node (ref "U1") (pin "32") (pinfunction "P1_4_32") (pintype "bidirectional+no_connect"))
    )
    (net (code "34") (name "unconnected-(U1-P1_5-Pad33)") (class "Default")
      (node (ref "U1") (pin "33") (pinfunction "P1_5_33") (pintype "bidirectional+no_connect"))
    )
    (net (code "35") (name "unconnected-(U1-P1_6-Pad34)") (class "Default")
      (node (ref "U1") (pin "34") (pinfunction "P1_6_34") (pintype "bidirectional+no_connect"))
    )
    (net (code "36") (name "unconnected-(U1-P2_0-Pad37)") (class "Default")
      (node (ref "U1") (pin "37") (pinfunction "P2_0_37") (pintype "bidirectional+no_connect"))
    )
    (net (code "37") (name "unconnected-(U1-P2_1-Pad38)") (class "Default")
      (node (ref "U1") (pin "38") (pinfunction "P2_1_38") (pintype "bidirectional+no_connect"))
    )
    (net (code "38") (name "unconnected-(U1-P2_2-Pad39)") (class "Default")
      (node (ref "U1") (pin "39") (pinfunction "P2_2_39") (pintype "bidirectional+no_connect"))
    )
    (net (code "39") (name "unconnected-(U1-P2_4-Pad41)") (class "Default")
      (node (ref "U1") (pin "41") (pinfunction "P2_4_41") (pintype "bidirectional+no_connect"))
    )
    (net (code "40") (name "unconnected-(U1-P2_5-Pad42)") (class "Default")
      (node (ref "U1") (pin "42") (pinfunction "P2_5_42") (pintype "bidirectional+no_connect"))
    )
    (net (code "41") (name "unconnected-(U1-P2_6-Pad43)") (class "Default")
      (node (ref "U1") (pin "43") (pinfunction "P2_6_43") (pintype "bidirectional+no_connect"))
    )
    (net (code "42") (name "unconnected-(U1-P2_7-Pad44)") (class "Default")
      (node (ref "U1") (pin "44") (pinfunction "P2_7_44") (pintype "bidirectional+no_connect"))
    )
    (net (code "43") (name "unconnected-(U1-P3_0-Pad47)") (class "Default")
      (node (ref "U1") (pin "47") (pinfunction "P3_0_47") (pintype "bidirectional+no_connect"))
    )
    (net (code "44") (name "unconnected-(U1-P3_1-Pad48)") (class "Default")
      (node (ref "U1") (pin "48") (pinfunction "P3_1_48") (pintype "bidirectional+no_connect"))
    )
    (net (code "45") (name "unconnected-(U1-P3_2-Pad49)") (class "Default")
      (node (ref "U1") (pin "49") (pinfunction "P3_2_49") (pintype "bidirectional+no_connect"))
    )
    (net (code "46") (name "unconnected-(U1-P3_3-Pad50)") (class "Default")
      (node (ref "U1") (pin "50") (pinfunction "P3_3_50") (pintype "bidirectional+no_connect"))
    )
    (net (code "47") (name "unconnected-(U1-P3_4-Pad51)") (class "Default")
      (node (ref "U1") (pin "51") (pinfunction "P3_4_51") (pintype "bidirectional+no_connect"))
    )
    (net (code "48") (name "unconnected-(U1-P3_5-Pad52)") (class "Default")
      (node (ref "U1") (pin "52") (pinfunction "P3_5_52") (pintype "bidirectional+no_connect"))
    )
    (net (code "49") (name "unconnected-(U1-P3_6-Pad53)") (class "Default")
      (node (ref "U1") (pin "53") (pinfunction "P3_6_53") (pintype "bidirectional+no_connect"))
    )
    (net (code "50") (name "unconnected-(U1-P4_0-Pad5)") (class "Default")
      (node (ref "U1") (pin "5") (pinfunction "P4_0_5") (pintype "bidirectional+no_connect"))
    )
    (net (code "51") (name "unconnected-(U1-P4_1-Pad6)") (class "Default")
      (node (ref "U1") (pin "6") (pinfunction "P4_1_6") (pintype "bidirectional+no_connect"))
    )
    (net (code "52") (name "unconnected-(U1-P5_0-Pad7)") (class "Default")
      (node (ref "U1") (pin "7") (pinfunction "P5_0_7") (pintype "bidirectional+no_connect"))
    )
    (net (code "53") (name "unconnected-(U1-P5_1-Pad8)") (class "Default")
      (node (ref "U1") (pin "8") (pinfunction "P5_1_8") (pintype "bidirectional+no_connect"))
    )
  )
)
